# 6Taster_RGB-LED.net
KiCad netlist of a schematic drawn in EAGLE
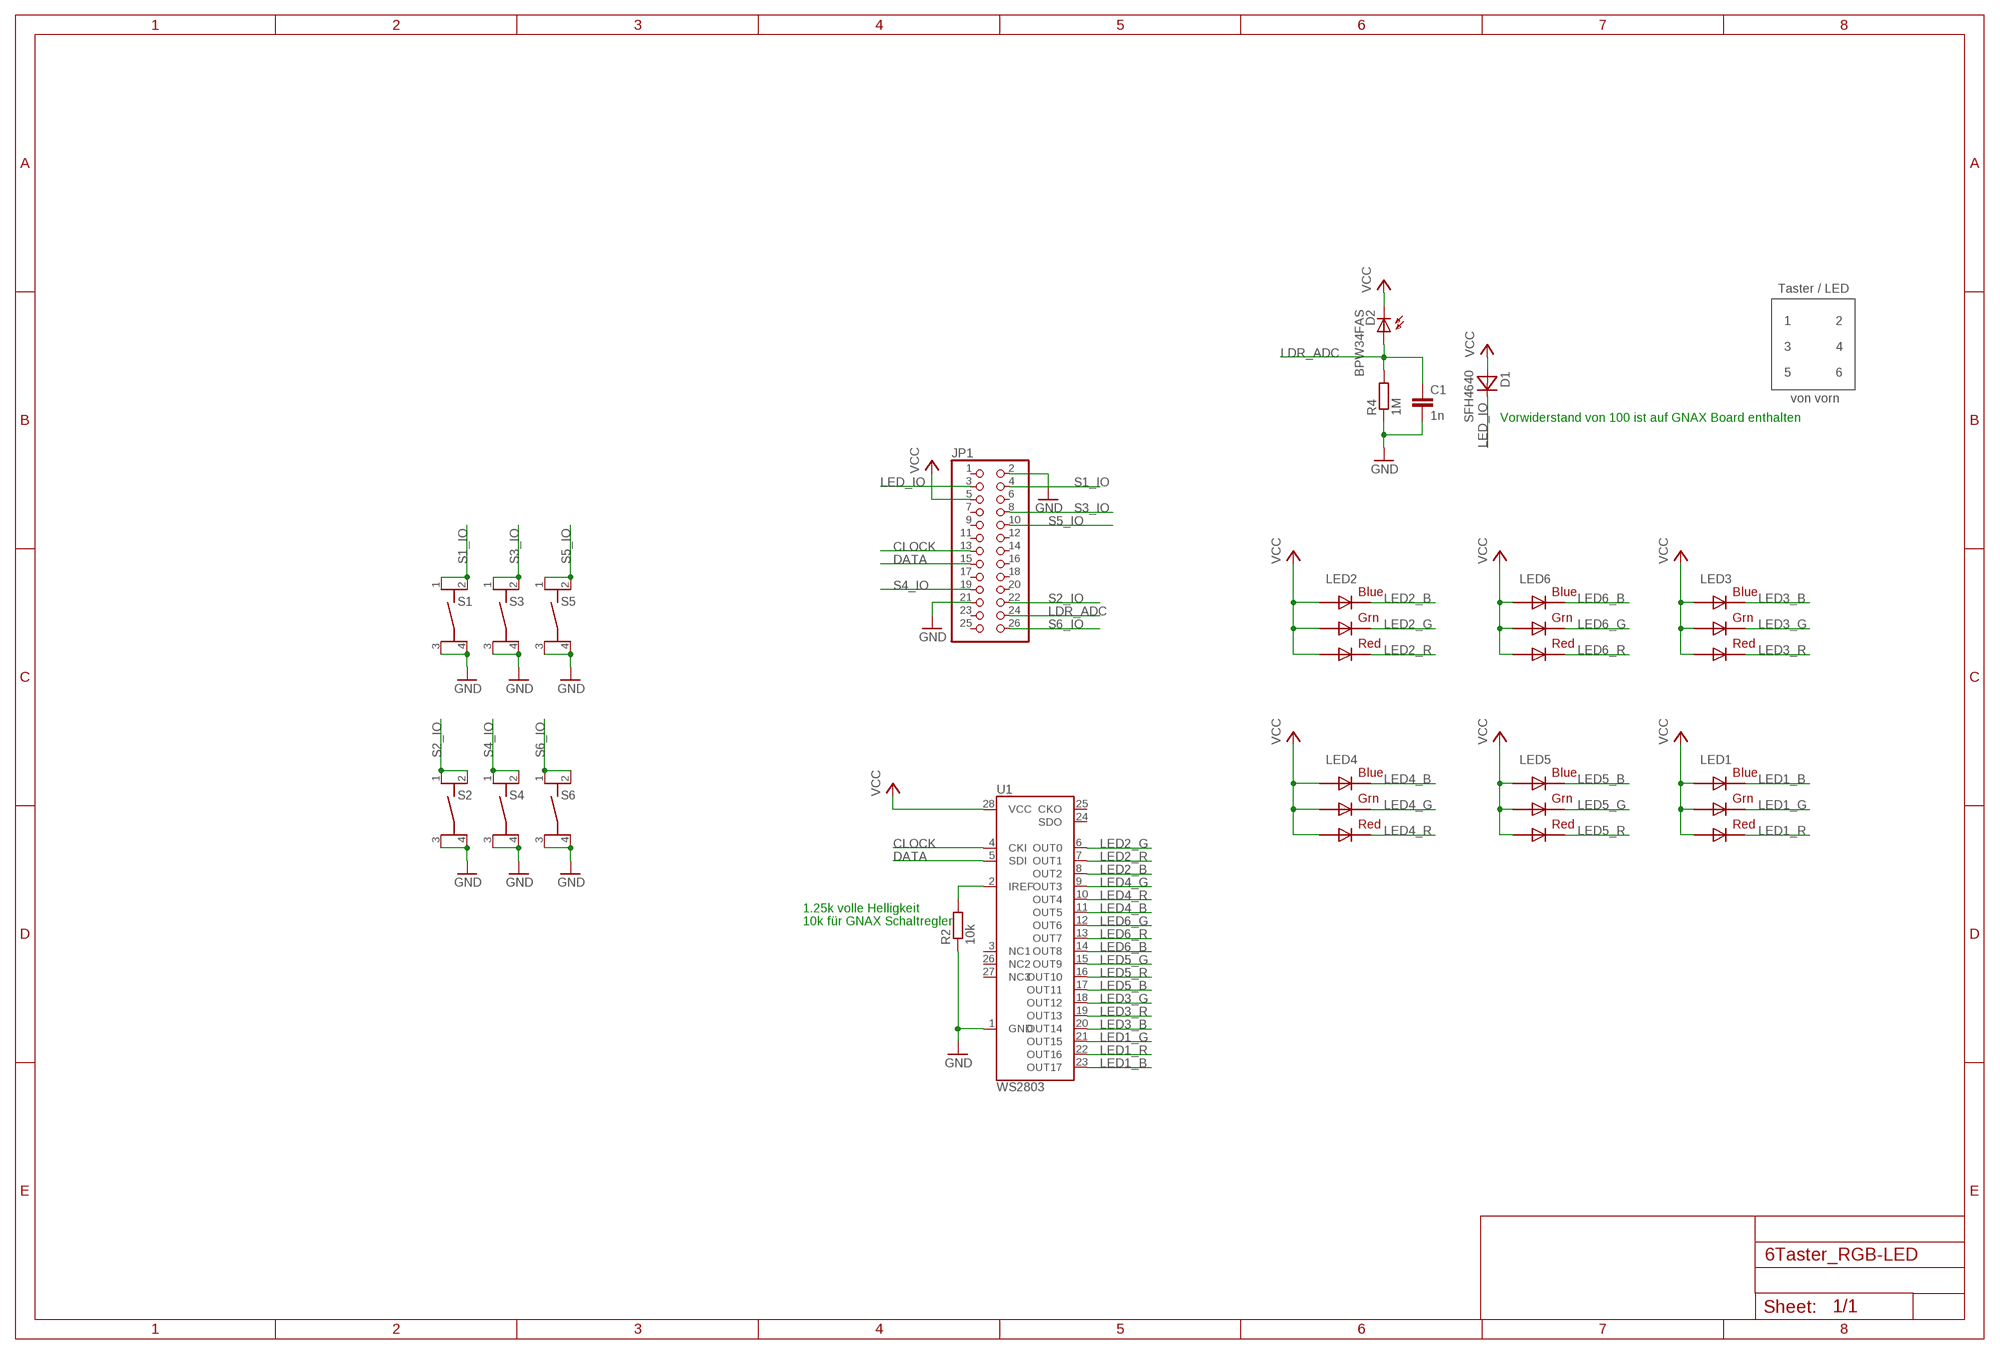
[diagram p0: schematic, sheet 1]

(export (version "E")
  (design (tool "Eeschema 10.0.6"))
  (components
    (comp (ref "C1")
      (value "1n")
      (footprint "eagle-import:C0805")
      (libsource (lib "eagle-import") (part "C-EUC0805"))
    )
    (comp (ref "D1")
      (value "SFH4640")
      (footprint "eagle-import:SFH4640")
      (libsource (lib "eagle-import") (part "SFH4640"))
    )
    (comp (ref "D2")
      (value "BPW34FAS")
      (footprint "eagle-import:BPW34FAS")
      (libsource (lib "eagle-import") (part "BPW34FAS"))
    )
    (comp (ref "JP1")
      (value "PINHD-2X13_2.54-SMD")
      (footprint "eagle-import:2X13SMD")
      (libsource (lib "eagle-import") (part "PINHD-2X13_2.54-SMD"))
    )
    (comp (ref "LED1")
      (value "RGB")
      (footprint "eagle-import:RGBLED5050")
      (libsource (lib "eagle-import") (part "RGBLED5050"))
    )
    (comp (ref "LED2")
      (value "RGB")
      (footprint "eagle-import:RGBLED5050")
      (libsource (lib "eagle-import") (part "RGBLED5050"))
    )
    (comp (ref "LED3")
      (value "RGB")
      (footprint "eagle-import:RGBLED5050")
      (libsource (lib "eagle-import") (part "RGBLED5050"))
    )
    (comp (ref "LED4")
      (value "RGB")
      (footprint "eagle-import:RGBLED5050")
      (libsource (lib "eagle-import") (part "RGBLED5050"))
    )
    (comp (ref "LED5")
      (value "RGB")
      (footprint "eagle-import:RGBLED5050")
      (libsource (lib "eagle-import") (part "RGBLED5050"))
    )
    (comp (ref "LED6")
      (value "RGB")
      (footprint "eagle-import:RGBLED5050")
      (libsource (lib "eagle-import") (part "RGBLED5050"))
    )
    (comp (ref "R2")
      (value "10k")
      (footprint "eagle-import:R0805")
      (libsource (lib "eagle-import") (part "R-EU_R0805"))
    )
    (comp (ref "R4")
      (value "1M")
      (footprint "eagle-import:R0805")
      (libsource (lib "eagle-import") (part "R-EU_R0805"))
    )
    (comp (ref "S1")
      (value "TASTER_9314SMD")
      (footprint "eagle-import:TASTER_9314")
      (libsource (lib "eagle-import") (part "TASTER_9314SMD"))
    )
    (comp (ref "S2")
      (value "TASTER_9314SMD")
      (footprint "eagle-import:TASTER_9314")
      (libsource (lib "eagle-import") (part "TASTER_9314SMD"))
    )
    (comp (ref "S3")
      (value "TASTER_9314SMD")
      (footprint "eagle-import:TASTER_9314")
      (libsource (lib "eagle-import") (part "TASTER_9314SMD"))
    )
    (comp (ref "S4")
      (value "TASTER_9314SMD")
      (footprint "eagle-import:TASTER_9314")
      (libsource (lib "eagle-import") (part "TASTER_9314SMD"))
    )
    (comp (ref "S5")
      (value "TASTER_9314SMD")
      (footprint "eagle-import:TASTER_9314")
      (libsource (lib "eagle-import") (part "TASTER_9314SMD"))
    )
    (comp (ref "S6")
      (value "TASTER_9314SMD")
      (footprint "eagle-import:TASTER_9314")
      (libsource (lib "eagle-import") (part "TASTER_9314SMD"))
    )
    (comp (ref "U1")
      (value "WS2803")
      (footprint "eagle-import:SOP-28")
      (libsource (lib "eagle-import") (part "WS2803"))
    )
  )
  (nets
    (net (code "1") (name "/CLOCK") (class "Default")
      (node (ref "JP1") (pin "13") (pinfunction "13_13") (pintype "passive"))
      (node (ref "U1") (pin "4") (pinfunction "CKI_4") (pintype "bidirectional"))
    )
    (net (code "2") (name "/DATA") (class "Default")
      (node (ref "JP1") (pin "15") (pinfunction "15_15") (pintype "passive"))
      (node (ref "U1") (pin "5") (pinfunction "SDI_5") (pintype "bidirectional"))
    )
    (net (code "3") (name "/LDR_ADC") (class "Default")
      (node (ref "C1") (pin "1") (pinfunction "1_1") (pintype "passive"))
      (node (ref "D2") (pin "ANODE") (pinfunction "A_ANODE") (pintype "passive"))
      (node (ref "JP1") (pin "24") (pinfunction "24_24") (pintype "passive"))
      (node (ref "R4") (pin "2") (pinfunction "2_2") (pintype "passive"))
    )
    (net (code "4") (name "/LED1_B") (class "Default")
      (node (ref "LED1") (pin "4") (pinfunction "BLUE_C_4") (pintype "bidirectional"))
      (node (ref "U1") (pin "23") (pinfunction "OUT17_23") (pintype "bidirectional"))
    )
    (net (code "5") (name "/LED1_G") (class "Default")
      (node (ref "LED1") (pin "6") (pinfunction "GREEN_C_6") (pintype "bidirectional"))
      (node (ref "U1") (pin "21") (pinfunction "OUT15_21") (pintype "bidirectional"))
    )
    (net (code "6") (name "/LED1_R") (class "Default")
      (node (ref "LED1") (pin "5") (pinfunction "RED_C_5") (pintype "bidirectional"))
      (node (ref "U1") (pin "22") (pinfunction "OUT16_22") (pintype "bidirectional"))
    )
    (net (code "7") (name "/LED2_B") (class "Default")
      (node (ref "LED2") (pin "4") (pinfunction "BLUE_C_4") (pintype "bidirectional"))
      (node (ref "U1") (pin "8") (pinfunction "OUT2_8") (pintype "bidirectional"))
    )
    (net (code "8") (name "/LED2_G") (class "Default")
      (node (ref "LED2") (pin "6") (pinfunction "GREEN_C_6") (pintype "bidirectional"))
      (node (ref "U1") (pin "6") (pinfunction "OUT0_6") (pintype "bidirectional"))
    )
    (net (code "9") (name "/LED2_R") (class "Default")
      (node (ref "LED2") (pin "5") (pinfunction "RED_C_5") (pintype "bidirectional"))
      (node (ref "U1") (pin "7") (pinfunction "OUT1_7") (pintype "bidirectional"))
    )
    (net (code "10") (name "/LED3_B") (class "Default")
      (node (ref "LED3") (pin "4") (pinfunction "BLUE_C_4") (pintype "bidirectional"))
      (node (ref "U1") (pin "20") (pinfunction "OUT14_20") (pintype "bidirectional"))
    )
    (net (code "11") (name "/LED3_G") (class "Default")
      (node (ref "LED3") (pin "6") (pinfunction "GREEN_C_6") (pintype "bidirectional"))
      (node (ref "U1") (pin "18") (pinfunction "OUT12_18") (pintype "bidirectional"))
    )
    (net (code "12") (name "/LED3_R") (class "Default")
      (node (ref "LED3") (pin "5") (pinfunction "RED_C_5") (pintype "bidirectional"))
      (node (ref "U1") (pin "19") (pinfunction "OUT13_19") (pintype "bidirectional"))
    )
    (net (code "13") (name "/LED4_B") (class "Default")
      (node (ref "LED4") (pin "4") (pinfunction "BLUE_C_4") (pintype "bidirectional"))
      (node (ref "U1") (pin "11") (pinfunction "OUT5_11") (pintype "bidirectional"))
    )
    (net (code "14") (name "/LED4_G") (class "Default")
      (node (ref "LED4") (pin "6") (pinfunction "GREEN_C_6") (pintype "bidirectional"))
      (node (ref "U1") (pin "9") (pinfunction "OUT3_9") (pintype "bidirectional"))
    )
    (net (code "15") (name "/LED4_R") (class "Default")
      (node (ref "LED4") (pin "5") (pinfunction "RED_C_5") (pintype "bidirectional"))
      (node (ref "U1") (pin "10") (pinfunction "OUT4_10") (pintype "bidirectional"))
    )
    (net (code "16") (name "/LED5_B") (class "Default")
      (node (ref "LED5") (pin "4") (pinfunction "BLUE_C_4") (pintype "bidirectional"))
      (node (ref "U1") (pin "17") (pinfunction "OUT11_17") (pintype "bidirectional"))
    )
    (net (code "17") (name "/LED5_G") (class "Default")
      (node (ref "LED5") (pin "6") (pinfunction "GREEN_C_6") (pintype "bidirectional"))
      (node (ref "U1") (pin "15") (pinfunction "OUT9_15") (pintype "bidirectional"))
    )
    (net (code "18") (name "/LED5_R") (class "Default")
      (node (ref "LED5") (pin "5") (pinfunction "RED_C_5") (pintype "bidirectional"))
      (node (ref "U1") (pin "16") (pinfunction "OUT10_16") (pintype "bidirectional"))
    )
    (net (code "19") (name "/LED6_B") (class "Default")
      (node (ref "LED6") (pin "4") (pinfunction "BLUE_C_4") (pintype "bidirectional"))
      (node (ref "U1") (pin "14") (pinfunction "OUT8_14") (pintype "bidirectional"))
    )
    (net (code "20") (name "/LED6_G") (class "Default")
      (node (ref "LED6") (pin "6") (pinfunction "GREEN_C_6") (pintype "bidirectional"))
      (node (ref "U1") (pin "12") (pinfunction "OUT6_12") (pintype "bidirectional"))
    )
    (net (code "21") (name "/LED6_R") (class "Default")
      (node (ref "LED6") (pin "5") (pinfunction "RED_C_5") (pintype "bidirectional"))
      (node (ref "U1") (pin "13") (pinfunction "OUT7_13") (pintype "bidirectional"))
    )
    (net (code "22") (name "/LED_IO") (class "Default")
      (node (ref "D1") (pin "KATHODE") (pinfunction "C_KATHODE") (pintype "passive"))
      (node (ref "JP1") (pin "3") (pinfunction "3_3") (pintype "passive"))
    )
    (net (code "23") (name "/S1_IO") (class "Default")
      (node (ref "JP1") (pin "4") (pinfunction "4_4") (pintype "passive"))
      (node (ref "S1") (pin "1") (pinfunction "1_1") (pintype "passive"))
      (node (ref "S1") (pin "2") (pinfunction "2_2") (pintype "passive"))
    )
    (net (code "24") (name "/S2_IO") (class "Default")
      (node (ref "JP1") (pin "22") (pinfunction "22_22") (pintype "passive"))
      (node (ref "S2") (pin "1") (pinfunction "1_1") (pintype "passive"))
      (node (ref "S2") (pin "2") (pinfunction "2_2") (pintype "passive"))
    )
    (net (code "25") (name "/S3_IO") (class "Default")
      (node (ref "JP1") (pin "8") (pinfunction "8_8") (pintype "passive"))
      (node (ref "S3") (pin "1") (pinfunction "1_1") (pintype "passive"))
      (node (ref "S3") (pin "2") (pinfunction "2_2") (pintype "passive"))
    )
    (net (code "26") (name "/S4_IO") (class "Default")
      (node (ref "JP1") (pin "19") (pinfunction "19_19") (pintype "passive"))
      (node (ref "S4") (pin "1") (pinfunction "1_1") (pintype "passive"))
      (node (ref "S4") (pin "2") (pinfunction "2_2") (pintype "passive"))
    )
    (net (code "27") (name "/S5_IO") (class "Default")
      (node (ref "JP1") (pin "10") (pinfunction "10_10") (pintype "passive"))
      (node (ref "S5") (pin "1") (pinfunction "1_1") (pintype "passive"))
      (node (ref "S5") (pin "2") (pinfunction "2_2") (pintype "passive"))
    )
    (net (code "28") (name "/S6_IO") (class "Default")
      (node (ref "JP1") (pin "26") (pinfunction "26_26") (pintype "passive"))
      (node (ref "S6") (pin "1") (pinfunction "1_1") (pintype "passive"))
      (node (ref "S6") (pin "2") (pinfunction "2_2") (pintype "passive"))
    )
    (net (code "29") (name "GND") (class "Default")
      (node (ref "C1") (pin "2") (pinfunction "2_2") (pintype "passive"))
      (node (ref "JP1") (pin "2") (pinfunction "2_2") (pintype "passive"))
      (node (ref "JP1") (pin "21") (pinfunction "21_21") (pintype "passive"))
      (node (ref "R2") (pin "1") (pinfunction "1_1") (pintype "passive"))
      (node (ref "R4") (pin "1") (pinfunction "1_1") (pintype "passive"))
      (node (ref "S1") (pin "3") (pinfunction "3_3") (pintype "passive"))
      (node (ref "S1") (pin "4") (pinfunction "4_4") (pintype "passive"))
      (node (ref "S2") (pin "3") (pinfunction "3_3") (pintype "passive"))
      (node (ref "S2") (pin "4") (pinfunction "4_4") (pintype "passive"))
      (node (ref "S3") (pin "3") (pinfunction "3_3") (pintype "passive"))
      (node (ref "S3") (pin "4") (pinfunction "4_4") (pintype "passive"))
      (node (ref "S4") (pin "3") (pinfunction "3_3") (pintype "passive"))
      (node (ref "S4") (pin "4") (pinfunction "4_4") (pintype "passive"))
      (node (ref "S5") (pin "3") (pinfunction "3_3") (pintype "passive"))
      (node (ref "S5") (pin "4") (pinfunction "4_4") (pintype "passive"))
      (node (ref "S6") (pin "3") (pinfunction "3_3") (pintype "passive"))
      (node (ref "S6") (pin "4") (pinfunction "4_4") (pintype "passive"))
      (node (ref "U1") (pin "1") (pinfunction "GND_1") (pintype "bidirectional"))
    )
    (net (code "30") (name "Net-(U1-IREF)") (class "Default")
      (node (ref "R2") (pin "2") (pinfunction "2_2") (pintype "passive"))
      (node (ref "U1") (pin "2") (pinfunction "IREF_2") (pintype "bidirectional"))
    )
    (net (code "31") (name "VCC") (class "Default")
      (node (ref "D1") (pin "ANODE") (pinfunction "A_ANODE") (pintype "passive"))
      (node (ref "D2") (pin "KATHODE") (pinfunction "C_KATHODE") (pintype "passive"))
      (node (ref "JP1") (pin "5") (pinfunction "5_5") (pintype "passive"))
      (node (ref "LED1") (pin "1") (pinfunction "GREEN_A_1") (pintype "bidirectional"))
      (node (ref "LED1") (pin "2") (pinfunction "RED_A_2") (pintype "bidirectional"))
      (node (ref "LED1") (pin "3") (pinfunction "BLUE_A_3") (pintype "bidirectional"))
      (node (ref "LED2") (pin "1") (pinfunction "GREEN_A_1") (pintype "bidirectional"))
      (node (ref "LED2") (pin "2") (pinfunction "RED_A_2") (pintype "bidirectional"))
      (node (ref "LED2") (pin "3") (pinfunction "BLUE_A_3") (pintype "bidirectional"))
      (node (ref "LED3") (pin "1") (pinfunction "GREEN_A_1") (pintype "bidirectional"))
      (node (ref "LED3") (pin "2") (pinfunction "RED_A_2") (pintype "bidirectional"))
      (node (ref "LED3") (pin "3") (pinfunction "BLUE_A_3") (pintype "bidirectional"))
      (node (ref "LED4") (pin "1") (pinfunction "GREEN_A_1") (pintype "bidirectional"))
      (node (ref "LED4") (pin "2") (pinfunction "RED_A_2") (pintype "bidirectional"))
      (node (ref "LED4") (pin "3") (pinfunction "BLUE_A_3") (pintype "bidirectional"))
      (node (ref "LED5") (pin "1") (pinfunction "GREEN_A_1") (pintype "bidirectional"))
      (node (ref "LED5") (pin "2") (pinfunction "RED_A_2") (pintype "bidirectional"))
      (node (ref "LED5") (pin "3") (pinfunction "BLUE_A_3") (pintype "bidirectional"))
      (node (ref "LED6") (pin "1") (pinfunction "GREEN_A_1") (pintype "bidirectional"))
      (node (ref "LED6") (pin "2") (pinfunction "RED_A_2") (pintype "bidirectional"))
      (node (ref "LED6") (pin "3") (pinfunction "BLUE_A_3") (pintype "bidirectional"))
      (node (ref "U1") (pin "28") (pinfunction "VCC_28") (pintype "bidirectional"))
    )
    (net (code "32") (name "unconnected-(JP1-Pad1)") (class "Default")
      (node (ref "JP1") (pin "1") (pinfunction "1_1") (pintype "passive"))
    )
    (net (code "33") (name "unconnected-(JP1-Pad6)") (class "Default")
      (node (ref "JP1") (pin "6") (pinfunction "6_6") (pintype "passive"))
    )
    (net (code "34") (name "unconnected-(JP1-Pad7)") (class "Default")
      (node (ref "JP1") (pin "7") (pinfunction "7_7") (pintype "passive"))
    )
    (net (code "35") (name "unconnected-(JP1-Pad9)") (class "Default")
      (node (ref "JP1") (pin "9") (pinfunction "9_9") (pintype "passive"))
    )
    (net (code "36") (name "unconnected-(JP1-Pad11)") (class "Default")
      (node (ref "JP1") (pin "11") (pinfunction "11_11") (pintype "passive"))
    )
    (net (code "37") (name "unconnected-(JP1-Pad12)") (class "Default")
      (node (ref "JP1") (pin "12") (pinfunction "12_12") (pintype "passive"))
    )
    (net (code "38") (name "unconnected-(JP1-Pad14)") (class "Default")
      (node (ref "JP1") (pin "14") (pinfunction "14_14") (pintype "passive"))
    )
    (net (code "39") (name "unconnected-(JP1-Pad16)") (class "Default")
      (node (ref "JP1") (pin "16") (pinfunction "16_16") (pintype "passive"))
    )
    (net (code "40") (name "unconnected-(JP1-Pad17)") (class "Default")
      (node (ref "JP1") (pin "17") (pinfunction "17_17") (pintype "passive"))
    )
    (net (code "41") (name "unconnected-(JP1-Pad18)") (class "Default")
      (node (ref "JP1") (pin "18") (pinfunction "18_18") (pintype "passive"))
    )
    (net (code "42") (name "unconnected-(JP1-Pad20)") (class "Default")
      (node (ref "JP1") (pin "20") (pinfunction "20_20") (pintype "passive"))
    )
    (net (code "43") (name "unconnected-(JP1-Pad23)") (class "Default")
      (node (ref "JP1") (pin "23") (pinfunction "23_23") (pintype "passive"))
    )
    (net (code "44") (name "unconnected-(JP1-Pad25)") (class "Default")
      (node (ref "JP1") (pin "25") (pinfunction "25_25") (pintype "passive"))
    )
    (net (code "45") (name "unconnected-(U1-CKO-Pad25)") (class "Default")
      (node (ref "U1") (pin "25") (pinfunction "CKO_25") (pintype "bidirectional"))
    )
    (net (code "46") (name "unconnected-(U1-NC1-Pad3)") (class "Default")
      (node (ref "U1") (pin "3") (pinfunction "NC1_3") (pintype "bidirectional"))
    )
    (net (code "47") (name "unconnected-(U1-NC2-Pad26)") (class "Default")
      (node (ref "U1") (pin "26") (pinfunction "NC2_26") (pintype "bidirectional"))
    )
    (net (code "48") (name "unconnected-(U1-NC3-Pad27)") (class "Default")
      (node (ref "U1") (pin "27") (pinfunction "NC3_27") (pintype "bidirectional"))
    )
    (net (code "49") (name "unconnected-(U1-SDO-Pad24)") (class "Default")
      (node (ref "U1") (pin "24") (pinfunction "SDO_24") (pintype "bidirectional"))
    )
  )
)
